# Works_006.net
KiCad netlist of a schematic drawn in EAGLE
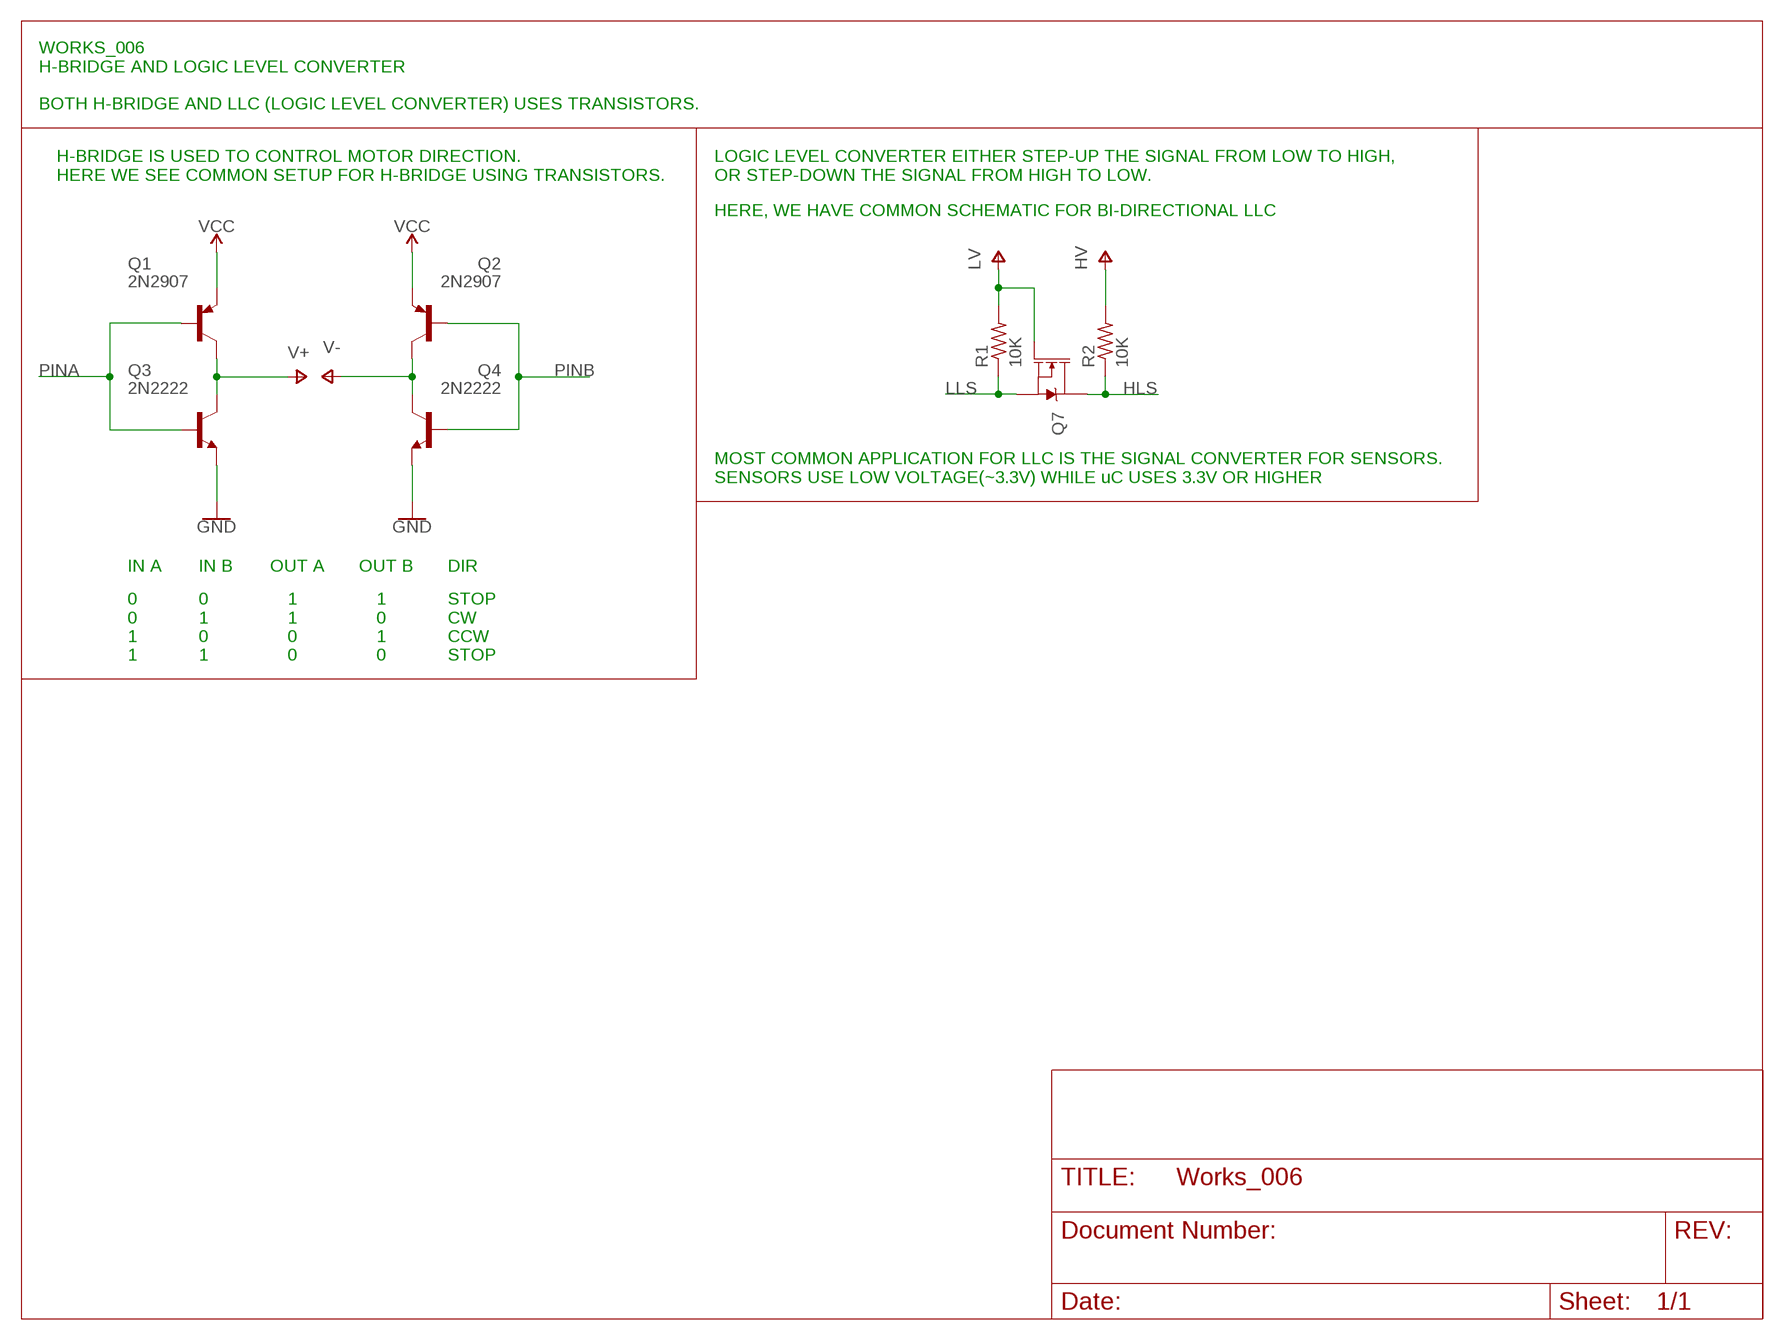
[diagram p0: schematic, sheet 1]

(export (version "E")
  (design (tool "Eeschema 10.0.6"))
  (components
    (comp (ref "Q1")
      (value "2N2907")
      (footprint "eagle-import:TO92-EBC-OVAL")
      (libsource (lib "eagle-import") (part "2N2907"))
    )
    (comp (ref "Q2")
      (value "2N2907")
      (footprint "eagle-import:TO92-EBC-OVAL")
      (libsource (lib "eagle-import") (part "2N2907"))
    )
    (comp (ref "Q3")
      (value "2N2222")
      (footprint "eagle-import:TO92-EBC-OVAL")
      (libsource (lib "eagle-import") (part "2N2222"))
    )
    (comp (ref "Q4")
      (value "2N2222")
      (footprint "eagle-import:TO92-EBC-OVAL")
      (libsource (lib "eagle-import") (part "2N2222"))
    )
    (comp (ref "Q7")
      (value "MOSFET-NCH-BSS138")
      (footprint "eagle-import:SOT23-3")
      (libsource (lib "eagle-import") (part "MOSFET-NCH-BSS138"))
    )
    (comp (ref "R1")
      (value "10K")
      (footprint "eagle-import:R0805")
      (libsource (lib "eagle-import") (part "R-US_R0805"))
    )
    (comp (ref "R2")
      (value "10K")
      (footprint "eagle-import:R0805")
      (libsource (lib "eagle-import") (part "R-US_R0805"))
    )
  )
  (nets
    (net (code "1") (name "/HLS") (class "Default")
      (node (ref "Q7") (pin "3") (pinfunction "D_3") (pintype "bidirectional"))
      (node (ref "R2") (pin "1") (pinfunction "1_1") (pintype "passive"))
    )
    (net (code "2") (name "/LLS") (class "Default")
      (node (ref "Q7") (pin "2") (pinfunction "S_2") (pintype "bidirectional"))
      (node (ref "R1") (pin "1") (pinfunction "1_1") (pintype "passive"))
    )
    (net (code "3") (name "/PINA") (class "Default")
      (node (ref "Q1") (pin "B") (pinfunction "B_B") (pintype "passive"))
      (node (ref "Q3") (pin "B") (pinfunction "B_B") (pintype "passive"))
    )
    (net (code "4") (name "/PINB") (class "Default")
      (node (ref "Q2") (pin "B") (pinfunction "B_B") (pintype "passive"))
      (node (ref "Q4") (pin "B") (pinfunction "B_B") (pintype "passive"))
    )
    (net (code "5") (name "GND") (class "Default")
      (node (ref "Q3") (pin "E") (pinfunction "E_E") (pintype "passive"))
      (node (ref "Q4") (pin "E") (pinfunction "E_E") (pintype "passive"))
    )
    (net (code "6") (name "HV") (class "Default")
      (node (ref "Q1") (pin "C") (pinfunction "C_C") (pintype "passive"))
      (node (ref "Q3") (pin "C") (pinfunction "C_C") (pintype "passive"))
      (node (ref "Q7") (pin "1") (pinfunction "G_1") (pintype "bidirectional"))
      (node (ref "R1") (pin "2") (pinfunction "2_2") (pintype "passive"))
      (node (ref "R2") (pin "2") (pinfunction "2_2") (pintype "passive"))
    )
    (net (code "7") (name "V-") (class "Default")
      (node (ref "Q2") (pin "C") (pinfunction "C_C") (pintype "passive"))
      (node (ref "Q4") (pin "C") (pinfunction "C_C") (pintype "passive"))
    )
    (net (code "8") (name "VCC") (class "Default")
      (node (ref "Q1") (pin "E") (pinfunction "E_E") (pintype "passive"))
      (node (ref "Q2") (pin "E") (pinfunction "E_E") (pintype "passive"))
    )
  )
)
